# DM1095_IMX214.net
KiCad netlist of a schematic drawn in Altium Designer
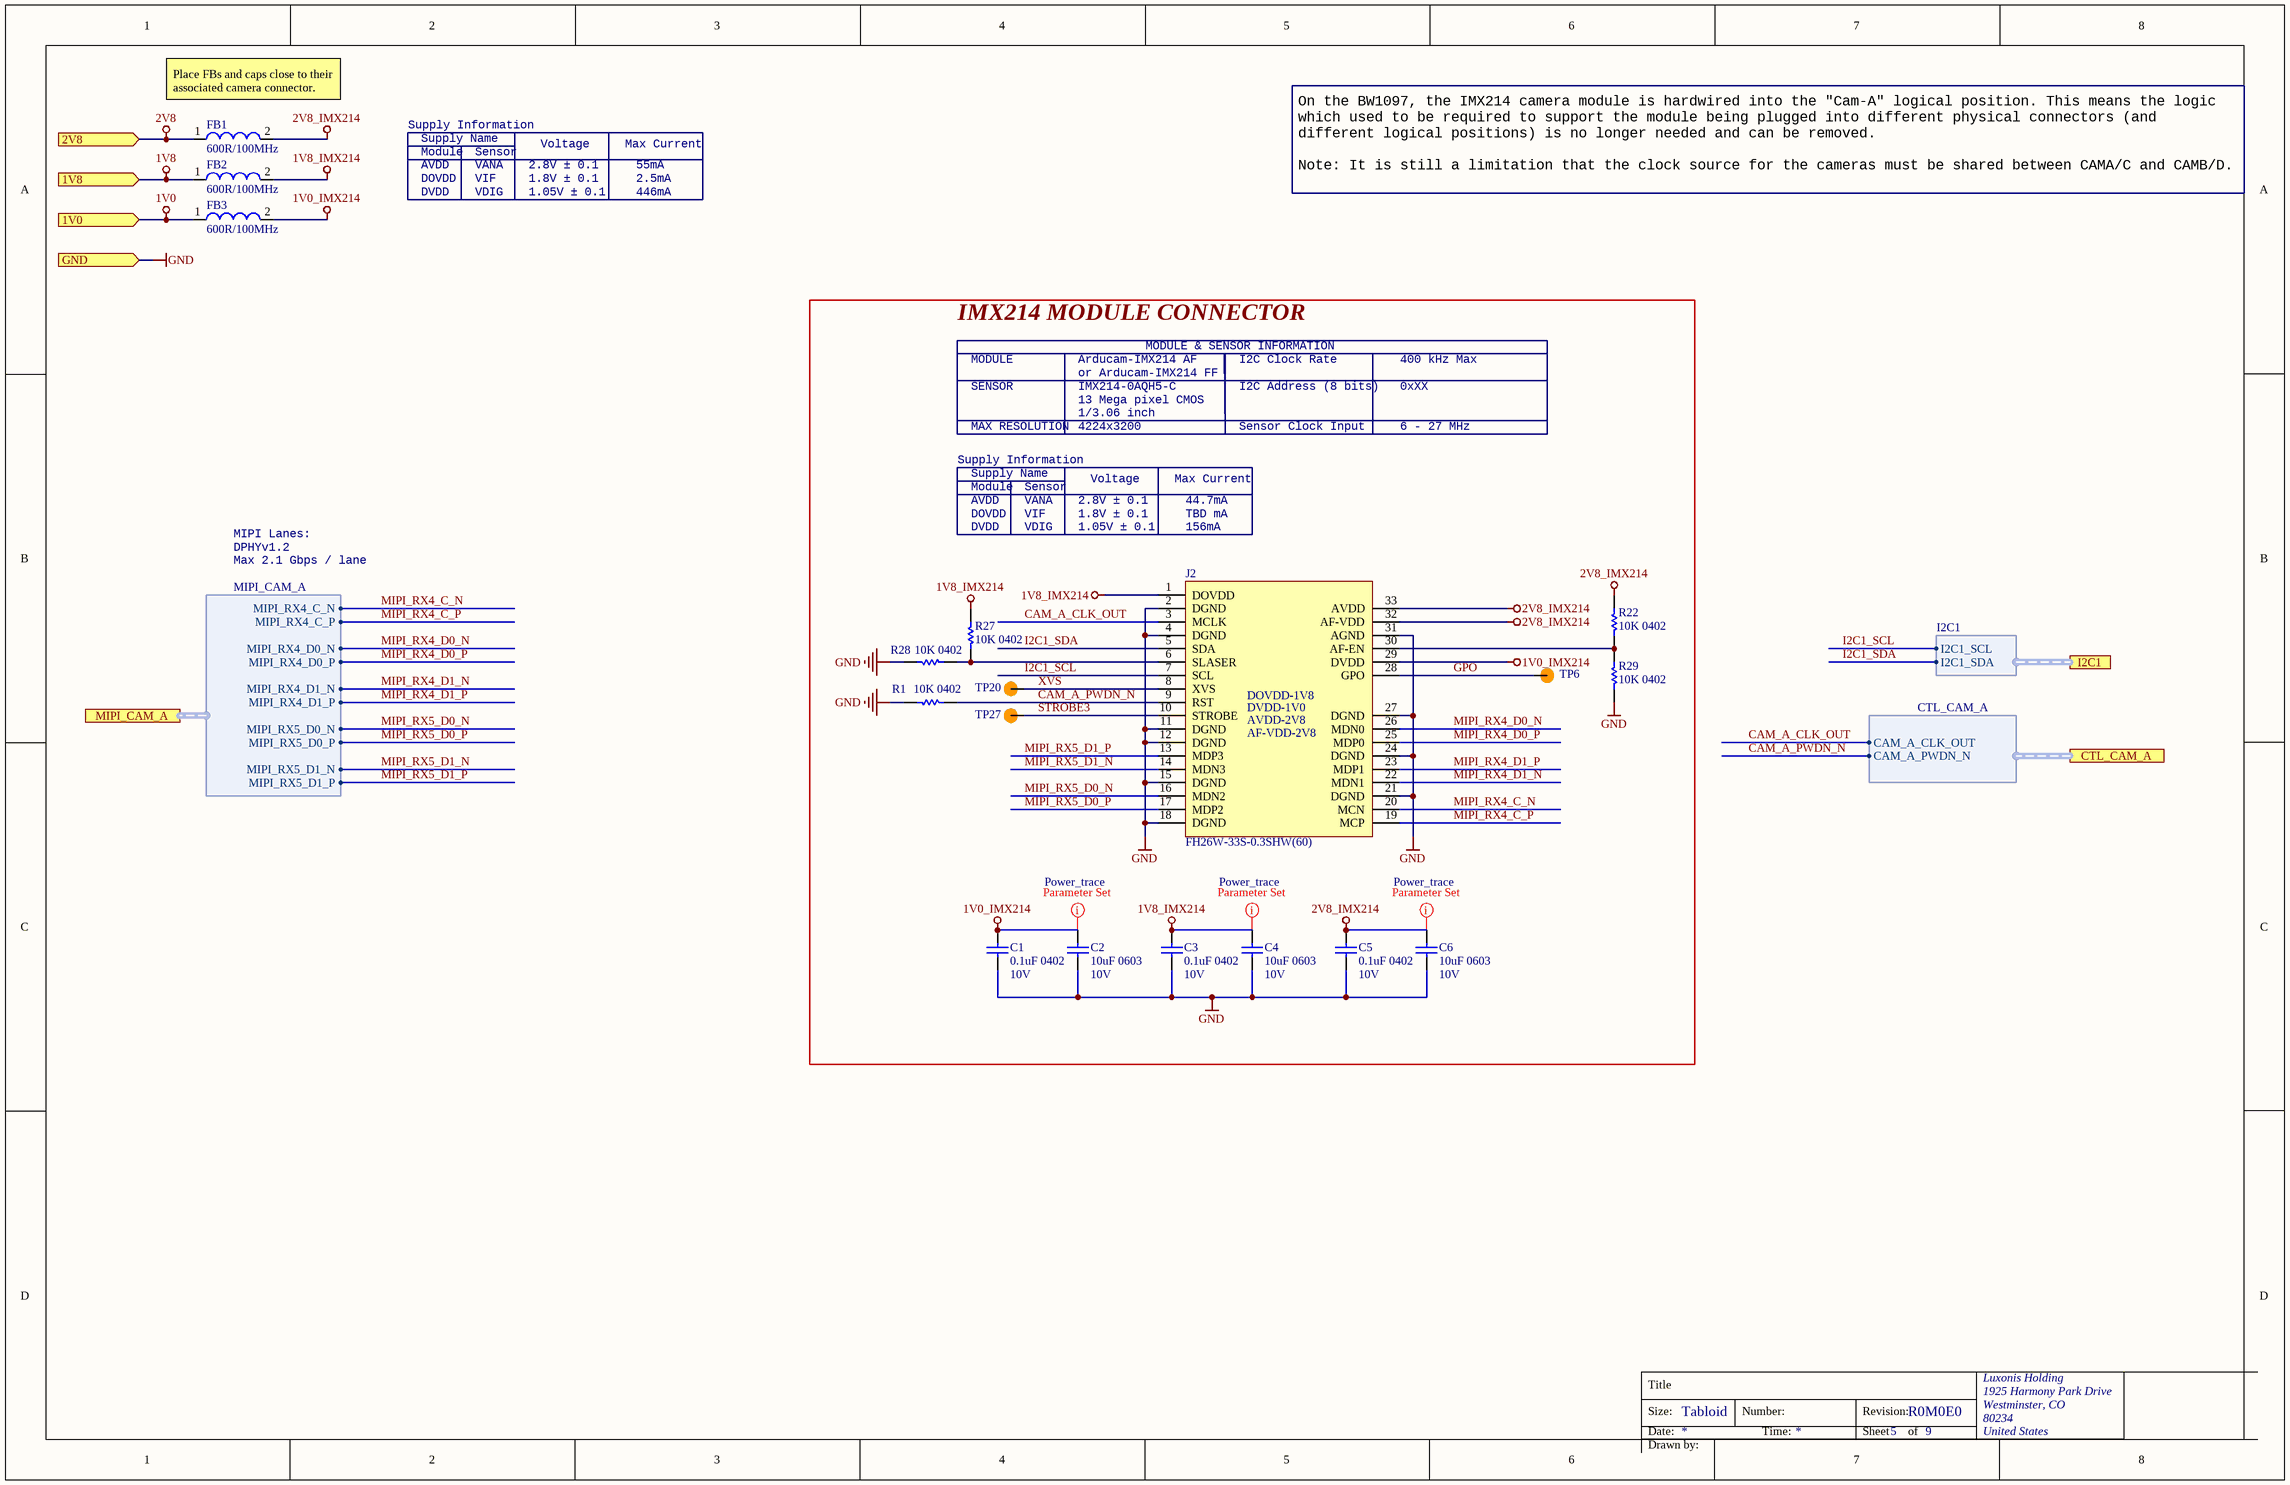
[diagram p0: DM1095_IMX214.SchDoc]

(export (version "E")
  (design (tool "Eeschema 10.0.6"))
  (components
    (comp (ref "C1")
      (value "0.1uF 0402")
      (footprint "CAP_Altium_Vault_Generic:CAPC0402(1005)70_L")
      (description "CAP CER 0.1UF 10V X7R 0402 5%")
      (fields (field (name "TOLERANCE") "5%") (field (name "VOLTAGE RATING") "10V"))
      (libsource (lib "LuxonisMaster") (part "GRM155R71A104JA01D"))
    )
    (comp (ref "C2")
      (value "10uF 0603")
      (footprint "CAP_Altium_Vault_Generic:CAPC0603(1608)100_L")
      (description "CAP CER 10UF 10V X5R 0603 20%")
      (fields (field (name "TOLERANCE") "20%") (field (name "VOLTAGE RATING") "10V"))
      (libsource (lib "LuxonisMaster") (part "GRM188R61A106ME69D"))
    )
    (comp (ref "C3")
      (value "0.1uF 0402")
      (footprint "CAP_Altium_Vault_Generic:CAPC0402(1005)70_L")
      (description "CAP CER 0.1UF 10V X7R 0402 5%")
      (fields (field (name "TOLERANCE") "5%") (field (name "VOLTAGE RATING") "10V"))
      (libsource (lib "LuxonisMaster") (part "GRM155R71A104JA01D"))
    )
    (comp (ref "C4")
      (value "10uF 0603")
      (footprint "CAP_Altium_Vault_Generic:CAPC0603(1608)100_L")
      (description "CAP CER 10UF 10V X5R 0603 20%")
      (fields (field (name "TOLERANCE") "20%") (field (name "VOLTAGE RATING") "10V"))
      (libsource (lib "LuxonisMaster") (part "GRM188R61A106ME69D"))
    )
    (comp (ref "C5")
      (value "0.1uF 0402")
      (footprint "CAP_Altium_Vault_Generic:CAPC0402(1005)70_L")
      (description "CAP CER 0.1UF 10V X7R 0402 5%")
      (fields (field (name "TOLERANCE") "5%") (field (name "VOLTAGE RATING") "10V"))
      (libsource (lib "LuxonisMaster") (part "GRM155R71A104JA01D"))
    )
    (comp (ref "C6")
      (value "10uF 0603")
      (footprint "CAP_Altium_Vault_Generic:CAPC0603(1608)100_L")
      (description "CAP CER 10UF 10V X5R 0603 20%")
      (fields (field (name "TOLERANCE") "20%") (field (name "VOLTAGE RATING") "10V"))
      (libsource (lib "LuxonisMaster") (part "GRM188R61A106ME69D"))
    )
    (comp (ref "FB1")
      (value "600R/100MHz")
      (footprint "LuxonisMaster:2508056017Y2")
      (description "FERRITE BEAD, 0.1OHM, 2A, 0805, 600R/100MHz")
      (fields (field (name "TOLERANCE") "25%"))
      (libsource (lib "LuxonisMaster") (part "2508056017Y2"))
    )
    (comp (ref "FB2")
      (value "600R/100MHz")
      (footprint "LuxonisMaster:2508056017Y2")
      (description "FERRITE BEAD, 0.1OHM, 2A, 0805, 600R/100MHz")
      (fields (field (name "TOLERANCE") "25%"))
      (libsource (lib "LuxonisMaster") (part "2508056017Y2"))
    )
    (comp (ref "FB3")
      (value "600R/100MHz")
      (footprint "LuxonisMaster:2508056017Y2")
      (description "FERRITE BEAD, 0.1OHM, 2A, 0805, 600R/100MHz")
      (fields (field (name "TOLERANCE") "25%"))
      (libsource (lib "LuxonisMaster") (part "2508056017Y2"))
    )
    (comp (ref "J2")
      (value "FH26W-33S-0.3SHW(60)")
      (footprint "ACIMX-214")
      (description "FFC/FPC Connector, 33 Contact(s), 1 Row(s), Female, Right Angle, Surface Mount Terminal")
      (libsource (lib "DM1095") (part "AC-IMX214_Connector"))
    )
    (comp (ref "R1")
      (value "10K 0402")
      (footprint "RES_Altium_Vault_Generic:RESC0402(1005)_L")
      (fields (field (name "TOLERANCE") "1%"))
      (libsource (lib "LuxonisMaster") (part "RC0402FR-1310KL"))
    )
    (comp (ref "R22")
      (value "10K 0402")
      (footprint "RES_Altium_Vault_Generic:RESC0402(1005)_L")
      (fields (field (name "TOLERANCE") "1%"))
      (libsource (lib "LuxonisMaster") (part "RC0402FR-1310KL"))
    )
    (comp (ref "R27")
      (value "10K 0402")
      (footprint "RES_Altium_Vault_Generic:RESC0402(1005)_L")
      (fields (field (name "TOLERANCE") "1%"))
      (libsource (lib "LuxonisMaster") (part "RC0402FR-1310KL"))
    )
    (comp (ref "R28")
      (value "10K 0402")
      (footprint "RES_Altium_Vault_Generic:RESC0402(1005)_L")
      (fields (field (name "TOLERANCE") "1%"))
      (libsource (lib "LuxonisMaster") (part "RC0402FR-1310KL"))
    )
    (comp (ref "R29")
      (value "10K 0402")
      (footprint "RES_Altium_Vault_Generic:RESC0402(1005)_L")
      (fields (field (name "TOLERANCE") "1%"))
      (libsource (lib "LuxonisMaster") (part "RC0402FR-1310KL"))
    )
    (comp (ref "TP6")
      (value "TP100_200_NS")
      (footprint "LuxonisMaster:TP100_200_NS")
      (libsource (lib "LuxonisMaster") (part "TEST_POINT"))
    )
    (comp (ref "TP20")
      (value "TP100_200_NS")
      (footprint "LuxonisMaster:TP100_200_NS")
      (libsource (lib "LuxonisMaster") (part "TEST_POINT"))
    )
    (comp (ref "TP27")
      (value "TP100_200_NS")
      (footprint "LuxonisMaster:TP100_200_NS")
      (libsource (lib "LuxonisMaster") (part "TEST_POINT"))
    )
  )
  (nets
    (net (code "4") (name "/CAM_A_CLK_OUT") (class "Default")
      (node (ref "J2") (pin "3") (pinfunction "MCLK_3") (pintype "passive"))
    )
    (net (code "5") (name "/CAM_A_PWDN_N") (class "Default")
      (node (ref "J2") (pin "9") (pinfunction "RST_9") (pintype "passive"))
      (node (ref "R1") (pin "1") (pinfunction "1_1") (pintype "passive"))
    )
    (net (code "6") (name "/GPO") (class "Default")
      (node (ref "J2") (pin "28") (pinfunction "GPO_28") (pintype "passive"))
      (node (ref "TP6") (pin "1") (pintype "passive"))
    )
    (net (code "7") (name "/I2C1_SCL") (class "Default")
      (node (ref "J2") (pin "7") (pinfunction "SCL_7") (pintype "passive"))
    )
    (net (code "8") (name "/I2C1_SDA") (class "Default")
      (node (ref "J2") (pin "5") (pinfunction "SDA_5") (pintype "passive"))
    )
    (net (code "9") (name "/MIPI_RX4_C_N") (class "Default")
      (node (ref "J2") (pin "20") (pinfunction "MCN_20") (pintype "passive"))
    )
    (net (code "10") (name "/MIPI_RX4_C_P") (class "Default")
      (node (ref "J2") (pin "19") (pinfunction "MCP_19") (pintype "passive"))
    )
    (net (code "11") (name "/MIPI_RX4_D0_N") (class "Default")
      (node (ref "J2") (pin "26") (pinfunction "MDN0_26") (pintype "passive"))
    )
    (net (code "12") (name "/MIPI_RX4_D0_P") (class "Default")
      (node (ref "J2") (pin "25") (pinfunction "MDP0_25") (pintype "passive"))
    )
    (net (code "13") (name "/MIPI_RX4_D1_N") (class "Default")
      (node (ref "J2") (pin "22") (pinfunction "MDN1_22") (pintype "passive"))
    )
    (net (code "14") (name "/MIPI_RX4_D1_P") (class "Default")
      (node (ref "J2") (pin "23") (pinfunction "MDP1_23") (pintype "passive"))
    )
    (net (code "15") (name "/MIPI_RX5_D0_N") (class "Default")
      (node (ref "J2") (pin "16") (pinfunction "MDN2_16") (pintype "passive"))
    )
    (net (code "16") (name "/MIPI_RX5_D0_P") (class "Default")
      (node (ref "J2") (pin "17") (pinfunction "MDP2_17") (pintype "passive"))
    )
    (net (code "17") (name "/MIPI_RX5_D1_N") (class "Default")
      (node (ref "J2") (pin "14") (pinfunction "MDN3_14") (pintype "passive"))
    )
    (net (code "18") (name "/MIPI_RX5_D1_P") (class "Default")
      (node (ref "J2") (pin "13") (pinfunction "MDP3_13") (pintype "passive"))
    )
    (net (code "19") (name "/STROBE3") (class "Default")
      (node (ref "J2") (pin "10") (pinfunction "STROBE_10") (pintype "passive"))
      (node (ref "TP27") (pin "1") (pintype "passive"))
    )
    (net (code "20") (name "/XVS") (class "Default")
      (node (ref "J2") (pin "8") (pinfunction "XVS_8") (pintype "passive"))
      (node (ref "TP20") (pin "1") (pintype "passive"))
    )
    (net (code "24") (name "1V0") (class "Default")
      (node (ref "FB3") (pin "1") (pinfunction "1_1") (pintype "passive"))
    )
    (net (code "25") (name "1V0_IMX214") (class "Default")
      (node (ref "C1") (pin "2") (pinfunction "2_2") (pintype "passive"))
      (node (ref "C2") (pin "2") (pinfunction "2_2") (pintype "passive"))
      (node (ref "FB3") (pin "2") (pinfunction "2_2") (pintype "passive"))
      (node (ref "J2") (pin "29") (pinfunction "DVDD_29") (pintype "passive"))
    )
    (net (code "26") (name "1V8") (class "Default")
      (node (ref "FB2") (pin "1") (pinfunction "1_1") (pintype "passive"))
    )
    (net (code "27") (name "1V8_IMX214") (class "Default")
      (node (ref "C3") (pin "2") (pinfunction "2_2") (pintype "passive"))
      (node (ref "C4") (pin "2") (pinfunction "2_2") (pintype "passive"))
      (node (ref "FB2") (pin "2") (pinfunction "2_2") (pintype "passive"))
      (node (ref "J2") (pin "1") (pinfunction "DOVDD_1") (pintype "passive"))
      (node (ref "R27") (pin "2") (pinfunction "2_2") (pintype "passive"))
    )
    (net (code "28") (name "2V8") (class "Default")
      (node (ref "FB1") (pin "1") (pinfunction "1_1") (pintype "passive"))
    )
    (net (code "29") (name "2V8_IMX214") (class "Default")
      (node (ref "C5") (pin "2") (pinfunction "2_2") (pintype "passive"))
      (node (ref "C6") (pin "2") (pinfunction "2_2") (pintype "passive"))
      (node (ref "FB1") (pin "2") (pinfunction "2_2") (pintype "passive"))
      (node (ref "J2") (pin "32") (pinfunction "AF-VDD_32") (pintype "passive"))
      (node (ref "J2") (pin "33") (pinfunction "AVDD_33") (pintype "passive"))
      (node (ref "R22") (pin "1") (pinfunction "1_1") (pintype "passive"))
    )
    (net (code "30") (name "GND") (class "Default")
      (node (ref "C1") (pin "1") (pinfunction "1_1") (pintype "passive"))
      (node (ref "C2") (pin "1") (pinfunction "1_1") (pintype "passive"))
      (node (ref "C3") (pin "1") (pinfunction "1_1") (pintype "passive"))
      (node (ref "C4") (pin "1") (pinfunction "1_1") (pintype "passive"))
      (node (ref "C5") (pin "1") (pinfunction "1_1") (pintype "passive"))
      (node (ref "C6") (pin "1") (pinfunction "1_1") (pintype "passive"))
      (node (ref "J2") (pin "11") (pinfunction "DGND_11") (pintype "passive"))
      (node (ref "J2") (pin "12") (pinfunction "DGND_12") (pintype "passive"))
      (node (ref "J2") (pin "15") (pinfunction "DGND_15") (pintype "passive"))
      (node (ref "J2") (pin "18") (pinfunction "DGND_18") (pintype "passive"))
      (node (ref "J2") (pin "2") (pinfunction "DGND_2") (pintype "passive"))
      (node (ref "J2") (pin "21") (pinfunction "DGND_21") (pintype "passive"))
      (node (ref "J2") (pin "24") (pinfunction "DGND_24") (pintype "passive"))
      (node (ref "J2") (pin "27") (pinfunction "DGND_27") (pintype "passive"))
      (node (ref "J2") (pin "31") (pinfunction "AGND_31") (pintype "passive"))
      (node (ref "J2") (pin "4") (pinfunction "DGND_4") (pintype "passive"))
      (node (ref "R1") (pin "2") (pinfunction "2_2") (pintype "passive"))
      (node (ref "R28") (pin "2") (pinfunction "2_2") (pintype "passive"))
      (node (ref "R29") (pin "2") (pinfunction "2_2") (pintype "passive"))
    )
    (net (code "31") (name "Net-(J2-AF-EN)") (class "Default")
      (node (ref "J2") (pin "30") (pinfunction "AF-EN_30") (pintype "passive"))
      (node (ref "R22") (pin "2") (pinfunction "2_2") (pintype "passive"))
      (node (ref "R29") (pin "1") (pinfunction "1_1") (pintype "passive"))
    )
    (net (code "32") (name "Net-(J2-SLASER)") (class "Default")
      (node (ref "J2") (pin "6") (pinfunction "SLASER_6") (pintype "passive"))
      (node (ref "R27") (pin "1") (pinfunction "1_1") (pintype "passive"))
      (node (ref "R28") (pin "1") (pinfunction "1_1") (pintype "passive"))
    )
  )
)
